# Door.net
KiCad netlist of a schematic drawn in EAGLE
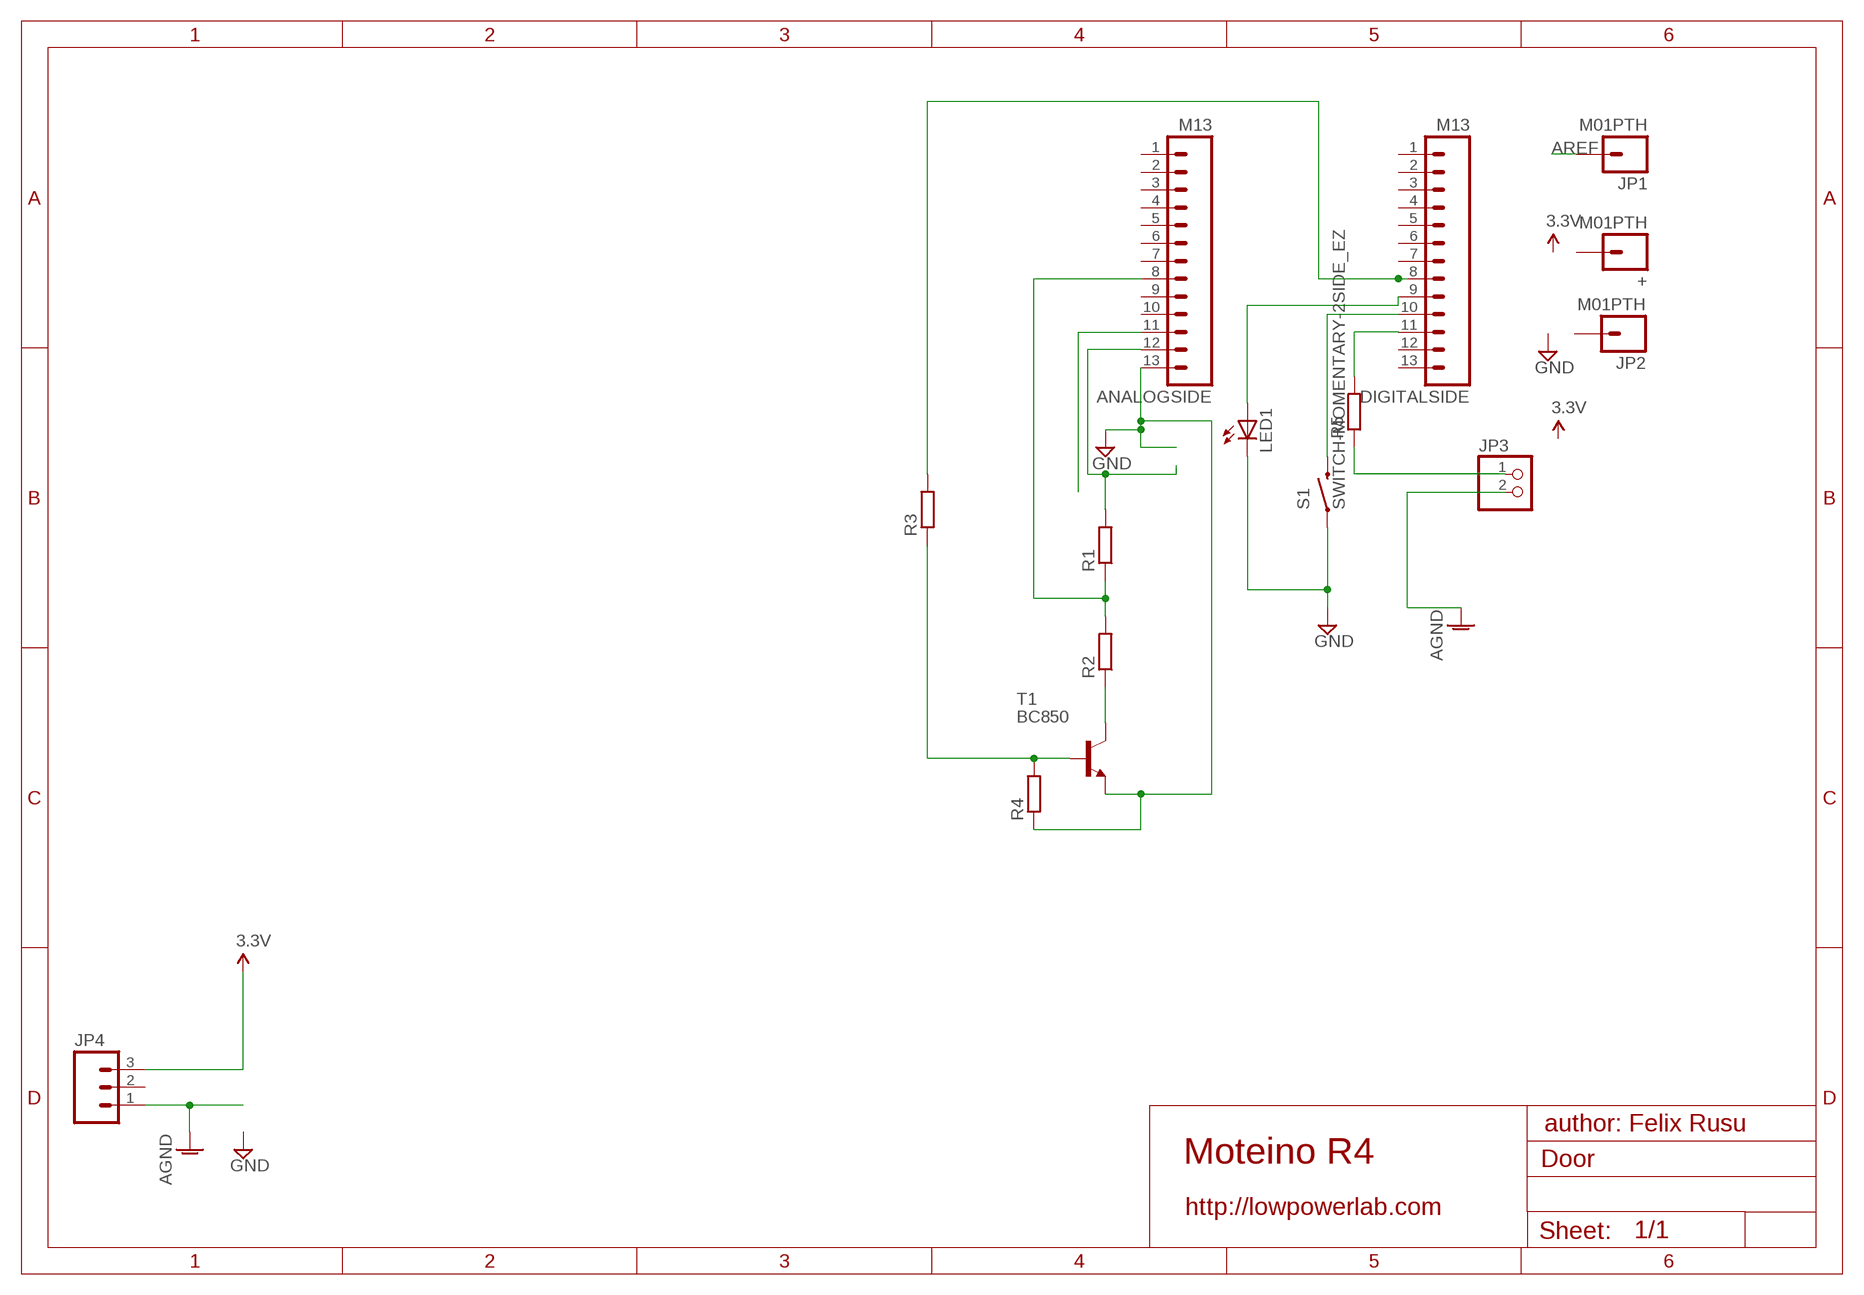
[diagram p0: schematic, sheet 1]

(export (version "E")
  (design (tool "Eeschema 10.0.6"))
  (components
    (comp (ref "+")
      (value "M01PTH")
      (footprint "eagle-import:1X01")
      (libsource (lib "eagle-import") (part "M01PTH"))
    )
    (comp (ref "ANALOGSIDE")
      (value "M13")
      (footprint "eagle-import:1X13")
      (libsource (lib "eagle-import") (part "M13"))
    )
    (comp (ref "DIGITALSIDE")
      (value "M13")
      (footprint "eagle-import:1X13")
      (libsource (lib "eagle-import") (part "M13"))
    )
    (comp (ref "JP1")
      (value "M01PTH")
      (footprint "eagle-import:1X01")
      (libsource (lib "eagle-import") (part "M01PTH"))
    )
    (comp (ref "JP2")
      (value "M01PTH")
      (footprint "eagle-import:1X01")
      (libsource (lib "eagle-import") (part "M01PTH"))
    )
    (comp (ref "JP3")
      (value "PINHD-1X2")
      (footprint "eagle-import:1X02")
      (libsource (lib "eagle-import") (part "PINHD-1X2"))
    )
    (comp (ref "JP4")
      (value "M03PTH")
      (footprint "eagle-import:1X03")
      (libsource (lib "eagle-import") (part "M03PTH"))
    )
    (comp (ref "LED1")
      (value "LED3MM")
      (footprint "eagle-import:LED3MM")
      (libsource (lib "eagle-import") (part "LED3MM"))
    )
    (comp (ref "R1")
      (value "R-EU_0204/7")
      (footprint "eagle-import:0204_7")
      (libsource (lib "eagle-import") (part "R-EU_0204/7"))
    )
    (comp (ref "R2")
      (value "R-EU_0204/7")
      (footprint "eagle-import:0204_7")
      (libsource (lib "eagle-import") (part "R-EU_0204/7"))
    )
    (comp (ref "R3")
      (value "R-EU_M1206")
      (footprint "eagle-import:M1206")
      (libsource (lib "eagle-import") (part "R-EU_M1206"))
    )
    (comp (ref "R4")
      (value "R-EU_M1206")
      (footprint "eagle-import:M1206")
      (libsource (lib "eagle-import") (part "R-EU_M1206"))
    )
    (comp (ref "R5")
      (value "R-EU_0204/7")
      (footprint "eagle-import:0204_7")
      (libsource (lib "eagle-import") (part "R-EU_0204/7"))
    )
    (comp (ref "S1")
      (value "SWITCH-MOMENTARY-2SIDE_EZ")
      (footprint "eagle-import:TACTILE-PTH-SIDEEZ")
      (libsource (lib "eagle-import") (part "SWITCH-MOMENTARY-2SIDE_EZ"))
    )
    (comp (ref "T1")
      (value "BC850")
      (footprint "eagle-import:SOT23")
      (libsource (lib "eagle-import") (part "BC850"))
    )
  )
  (nets
    (net (code "1") (name "/AREF") (class "Default")
      (node (ref "JP1") (pin "1") (pinfunction "1_1") (pintype "passive"))
    )
    (net (code "2") (name "3.3V") (class "Default")
      (node (ref "JP4") (pin "3") (pinfunction "3_3") (pintype "passive"))
    )
    (net (code "3") (name "AGND") (class "Default")
      (node (ref "JP3") (pin "2") (pinfunction "2_2") (pintype "passive"))
      (node (ref "JP4") (pin "1") (pinfunction "1_1") (pintype "passive"))
    )
    (net (code "4") (name "GND") (class "Default")
      (node (ref "ANALOGSIDE") (pin "13") (pinfunction "13_13") (pintype "passive"))
      (node (ref "LED1") (pin "K") (pinfunction "C_K") (pintype "passive"))
      (node (ref "R4") (pin "1") (pinfunction "1_1") (pintype "passive"))
      (node (ref "S1") (pin "1") (pinfunction "1_1") (pintype "passive"))
      (node (ref "T1") (pin "2") (pinfunction "E_2") (pintype "passive"))
    )
    (net (code "5") (name "Net-(ANALOGSIDE-Pad8)") (class "Default")
      (node (ref "ANALOGSIDE") (pin "8") (pinfunction "8_8") (pintype "passive"))
      (node (ref "R1") (pin "1") (pinfunction "1_1") (pintype "passive"))
      (node (ref "R2") (pin "2") (pinfunction "2_2") (pintype "passive"))
    )
    (net (code "6") (name "Net-(ANALOGSIDE-Pad12)") (class "Default")
      (node (ref "ANALOGSIDE") (pin "12") (pinfunction "12_12") (pintype "passive"))
      (node (ref "R1") (pin "2") (pinfunction "2_2") (pintype "passive"))
    )
    (net (code "7") (name "Net-(DIGITALSIDE-Pad8)") (class "Default")
      (node (ref "DIGITALSIDE") (pin "8") (pinfunction "8_8") (pintype "passive"))
      (node (ref "R3") (pin "2") (pinfunction "2_2") (pintype "passive"))
    )
    (net (code "8") (name "Net-(DIGITALSIDE-Pad9)") (class "Default")
      (node (ref "DIGITALSIDE") (pin "9") (pinfunction "9_9") (pintype "passive"))
      (node (ref "LED1") (pin "A") (pinfunction "A_A") (pintype "passive"))
    )
    (net (code "9") (name "Net-(DIGITALSIDE-Pad10)") (class "Default")
      (node (ref "DIGITALSIDE") (pin "10") (pinfunction "10_10") (pintype "passive"))
      (node (ref "S1") (pin "2") (pinfunction "2_2") (pintype "passive"))
    )
    (net (code "10") (name "Net-(DIGITALSIDE-Pad11)") (class "Default")
      (node (ref "DIGITALSIDE") (pin "11") (pinfunction "11_11") (pintype "passive"))
      (node (ref "R5") (pin "2") (pinfunction "2_2") (pintype "passive"))
    )
    (net (code "11") (name "Net-(JP3-Pad1)") (class "Default")
      (node (ref "JP3") (pin "1") (pinfunction "1_1") (pintype "passive"))
      (node (ref "R5") (pin "1") (pinfunction "1_1") (pintype "passive"))
    )
    (net (code "12") (name "Net-(T1-B)") (class "Default")
      (node (ref "R3") (pin "1") (pinfunction "1_1") (pintype "passive"))
      (node (ref "R4") (pin "2") (pinfunction "2_2") (pintype "passive"))
      (node (ref "T1") (pin "1") (pinfunction "B_1") (pintype "passive"))
    )
    (net (code "13") (name "Net-(T1-C)") (class "Default")
      (node (ref "R2") (pin "1") (pinfunction "1_1") (pintype "passive"))
      (node (ref "T1") (pin "3") (pinfunction "C_3") (pintype "passive"))
    )
    (net (code "14") (name "unconnected-(+-Pad1)") (class "Default")
      (node (ref "+") (pin "1") (pinfunction "1_1") (pintype "passive"))
    )
    (net (code "15") (name "unconnected-(ANALOGSIDE-Pad1)") (class "Default")
      (node (ref "ANALOGSIDE") (pin "1") (pinfunction "1_1") (pintype "passive"))
    )
    (net (code "16") (name "unconnected-(ANALOGSIDE-Pad2)") (class "Default")
      (node (ref "ANALOGSIDE") (pin "2") (pinfunction "2_2") (pintype "passive"))
    )
    (net (code "17") (name "unconnected-(ANALOGSIDE-Pad3)") (class "Default")
      (node (ref "ANALOGSIDE") (pin "3") (pinfunction "3_3") (pintype "passive"))
    )
    (net (code "18") (name "unconnected-(ANALOGSIDE-Pad4)") (class "Default")
      (node (ref "ANALOGSIDE") (pin "4") (pinfunction "4_4") (pintype "passive"))
    )
    (net (code "19") (name "unconnected-(ANALOGSIDE-Pad5)") (class "Default")
      (node (ref "ANALOGSIDE") (pin "5") (pinfunction "5_5") (pintype "passive"))
    )
    (net (code "20") (name "unconnected-(ANALOGSIDE-Pad6)") (class "Default")
      (node (ref "ANALOGSIDE") (pin "6") (pinfunction "6_6") (pintype "passive"))
    )
    (net (code "21") (name "unconnected-(ANALOGSIDE-Pad7)") (class "Default")
      (node (ref "ANALOGSIDE") (pin "7") (pinfunction "7_7") (pintype "passive"))
    )
    (net (code "22") (name "unconnected-(ANALOGSIDE-Pad9)") (class "Default")
      (node (ref "ANALOGSIDE") (pin "9") (pinfunction "9_9") (pintype "passive"))
    )
    (net (code "23") (name "unconnected-(ANALOGSIDE-Pad10)") (class "Default")
      (node (ref "ANALOGSIDE") (pin "10") (pinfunction "10_10") (pintype "passive"))
    )
    (net (code "24") (name "unconnected-(ANALOGSIDE-Pad11)") (class "Default")
      (node (ref "ANALOGSIDE") (pin "11") (pinfunction "11_11") (pintype "passive"))
    )
    (net (code "25") (name "unconnected-(DIGITALSIDE-Pad1)") (class "Default")
      (node (ref "DIGITALSIDE") (pin "1") (pinfunction "1_1") (pintype "passive"))
    )
    (net (code "26") (name "unconnected-(DIGITALSIDE-Pad2)") (class "Default")
      (node (ref "DIGITALSIDE") (pin "2") (pinfunction "2_2") (pintype "passive"))
    )
    (net (code "27") (name "unconnected-(DIGITALSIDE-Pad3)") (class "Default")
      (node (ref "DIGITALSIDE") (pin "3") (pinfunction "3_3") (pintype "passive"))
    )
    (net (code "28") (name "unconnected-(DIGITALSIDE-Pad4)") (class "Default")
      (node (ref "DIGITALSIDE") (pin "4") (pinfunction "4_4") (pintype "passive"))
    )
    (net (code "29") (name "unconnected-(DIGITALSIDE-Pad5)") (class "Default")
      (node (ref "DIGITALSIDE") (pin "5") (pinfunction "5_5") (pintype "passive"))
    )
    (net (code "30") (name "unconnected-(DIGITALSIDE-Pad6)") (class "Default")
      (node (ref "DIGITALSIDE") (pin "6") (pinfunction "6_6") (pintype "passive"))
    )
    (net (code "31") (name "unconnected-(DIGITALSIDE-Pad7)") (class "Default")
      (node (ref "DIGITALSIDE") (pin "7") (pinfunction "7_7") (pintype "passive"))
    )
    (net (code "32") (name "unconnected-(DIGITALSIDE-Pad12)") (class "Default")
      (node (ref "DIGITALSIDE") (pin "12") (pinfunction "12_12") (pintype "passive"))
    )
    (net (code "33") (name "unconnected-(DIGITALSIDE-Pad13)") (class "Default")
      (node (ref "DIGITALSIDE") (pin "13") (pinfunction "13_13") (pintype "passive"))
    )
    (net (code "34") (name "unconnected-(JP2-Pad1)") (class "Default")
      (node (ref "JP2") (pin "1") (pinfunction "1_1") (pintype "passive"))
    )
    (net (code "35") (name "unconnected-(JP4-Pad2)") (class "Default")
      (node (ref "JP4") (pin "2") (pinfunction "2_2") (pintype "passive"))
    )
  )
)
